# SCH_esp32car_2026-05-05.net
KiCad netlist of a schematic drawn in EasyEDA
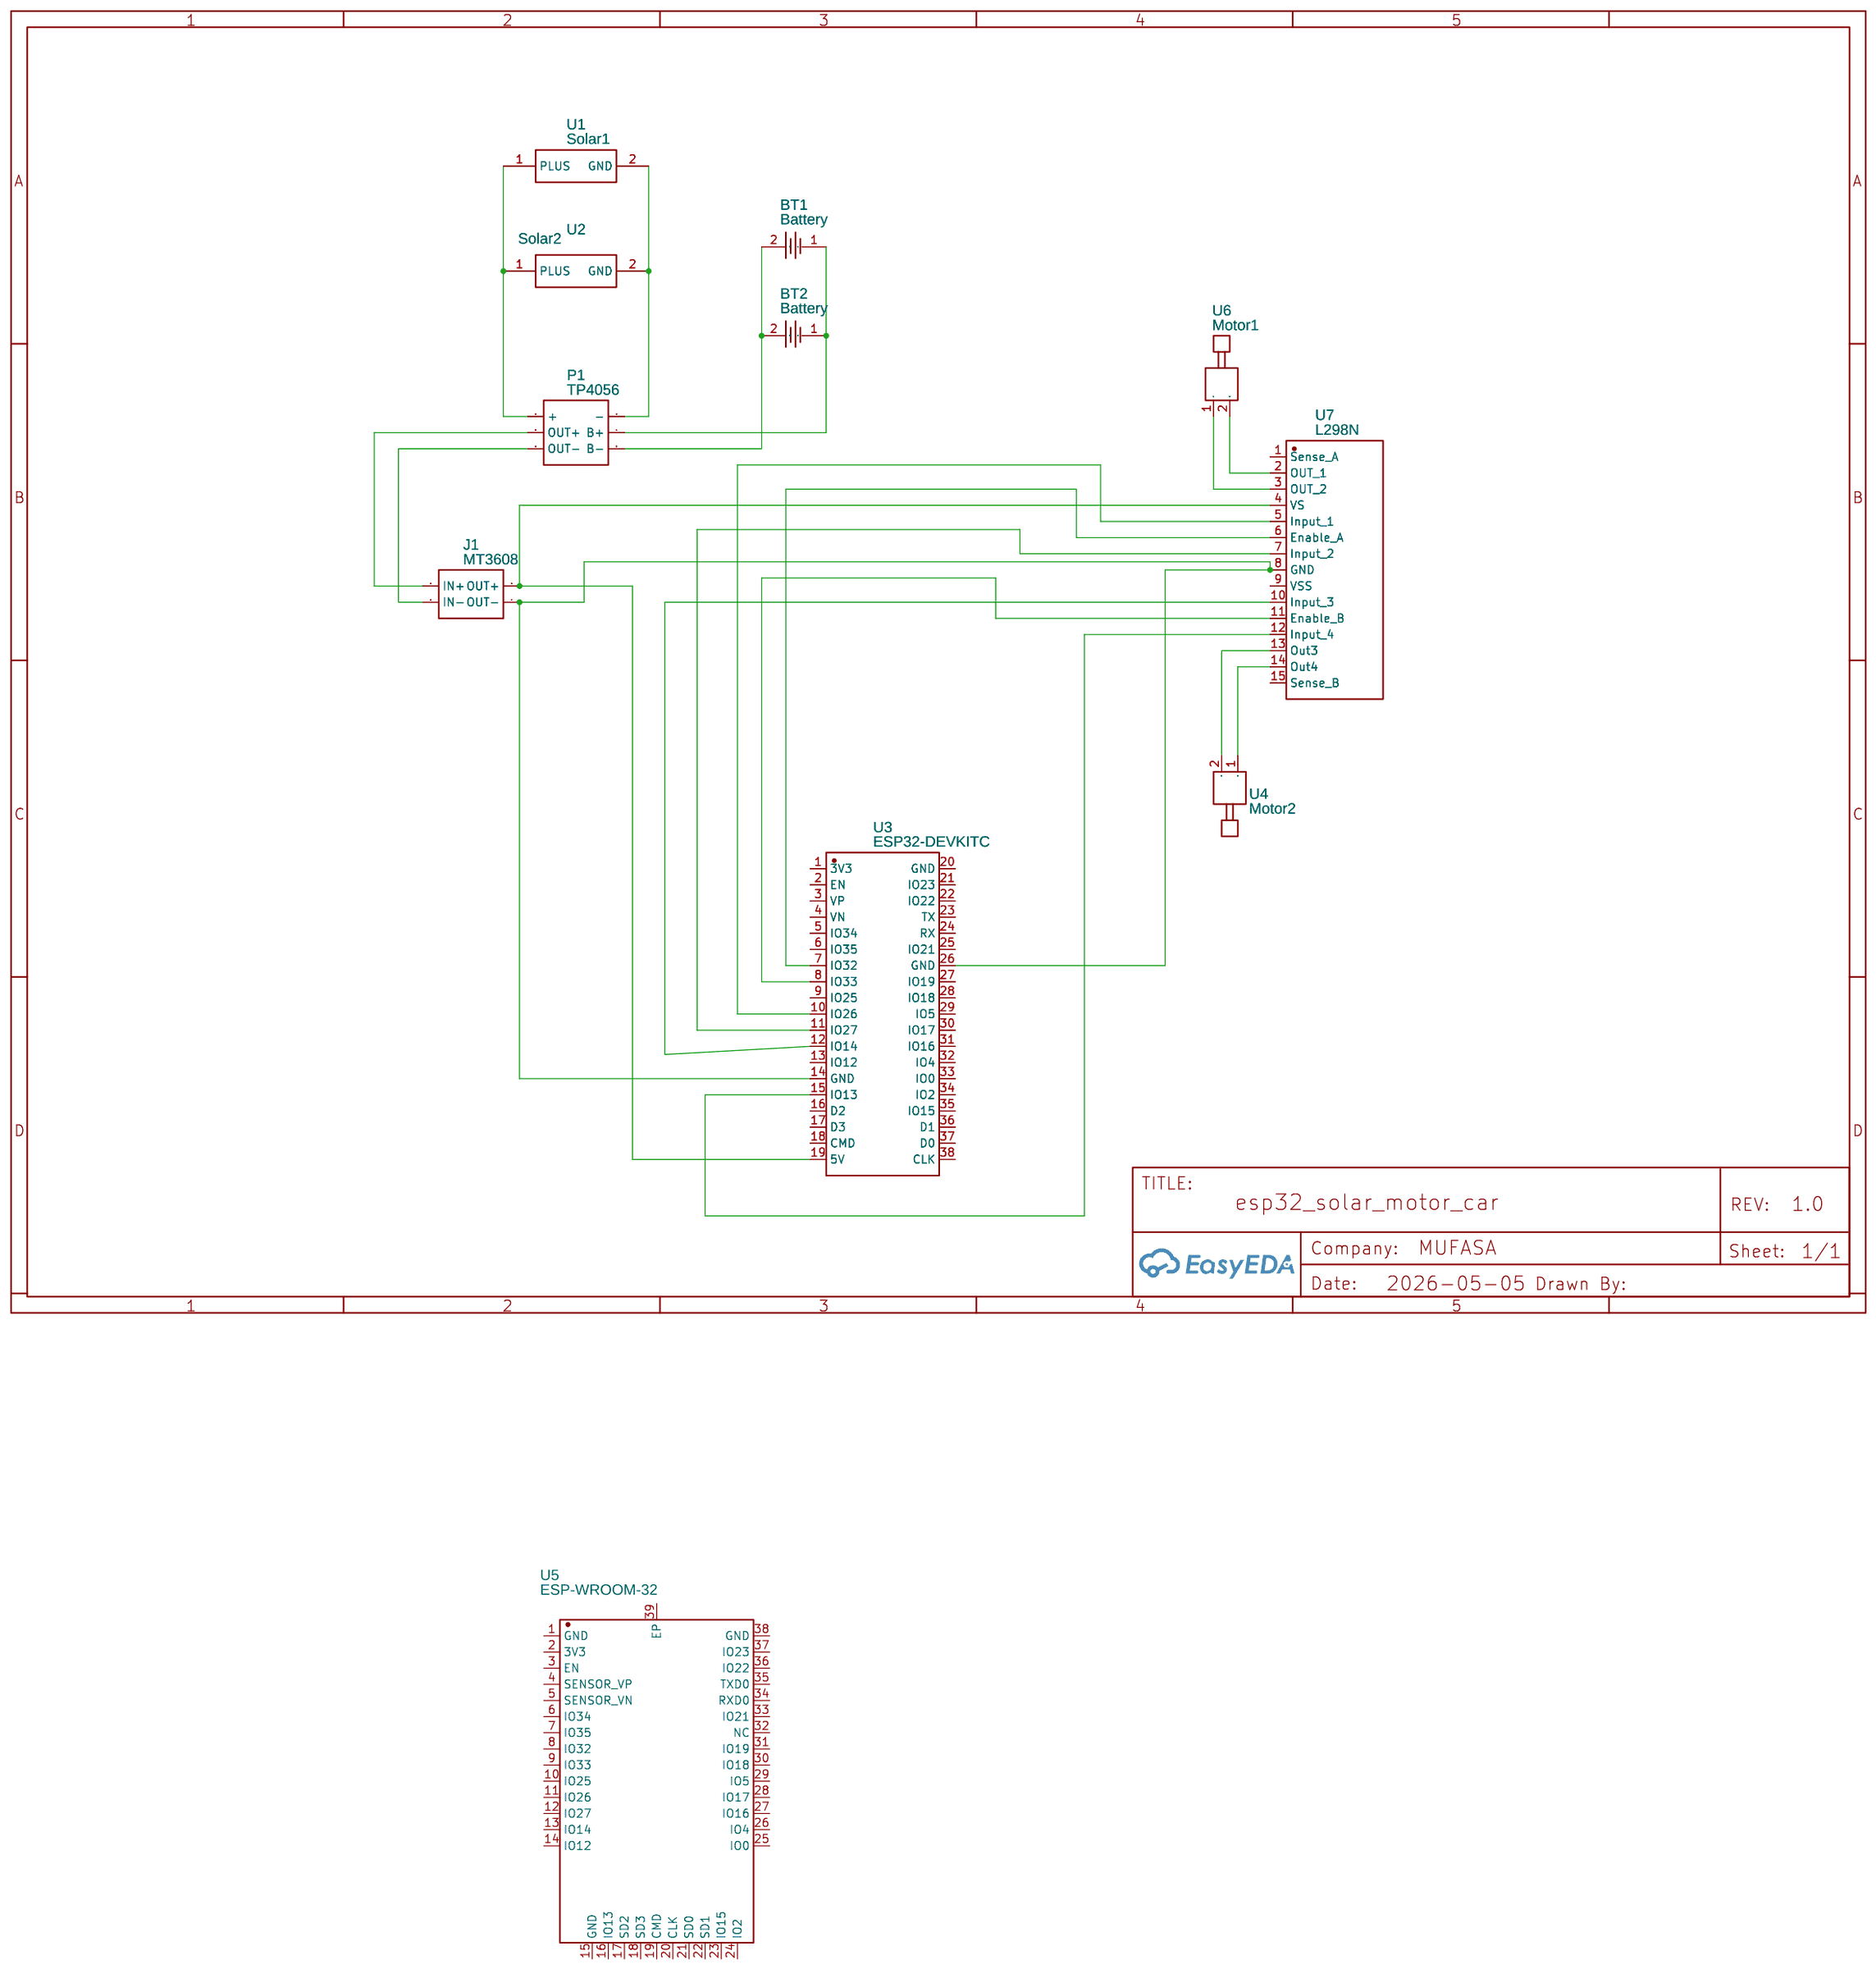
[diagram p0: schematic sheet]

(export (version "E")
  (design (tool "Eeschema 10.0.6"))
  (components
    (comp (ref "BT1")
      (value "Battery")
      (fields
        (field (name "Manufacturer Part") "BH-18650-B1BA002")
        (field (name "Manufacturer") "MYOUNG(美阳)")
      )
      (libsource (lib "") (part "BH-18650-B1BA002"))
    )
    (comp (ref "BT2")
      (value "Battery")
      (fields
        (field (name "Manufacturer Part") "BH-18650-B1BA002")
        (field (name "Manufacturer") "MYOUNG(美阳)")
      )
      (libsource (lib "") (part "BH-18650-B1BA002"))
    )
    (comp (ref "J1") (value "MT3608") (libsource (lib "") (part "HDR-M-2.54_2x2")))
    (comp (ref "P1")
      (value "TP4056")
      (fields (field (name "Manufacturer Part") "2X3 2.54mm IDC Box") (field (name "Manufacturer") "BOOMELE"))
      (libsource (lib "") (part "HDR-IDC-2.54-2X3P"))
    )
    (comp (ref "U1") (value "Solar1") (libsource (lib "") (part "KXOB25-01X8F-TB")))
    (comp (ref "U2") (value "Solar2") (libsource (lib "") (part "KXOB25-01X8F-TB")))
    (comp (ref "U3")
      (value "ESP32-DEVKITC")
      (fields
        (field (name "Manufacturer Part") "ESP32-DevKitC")
        (field (name "Manufacturer") "ESPRESSIF(乐鑫)")
      )
      (libsource (lib "") (part "ESP32-DEVKITC"))
    )
    (comp (ref "U4")
      (value "Motor2")
      (fields (field (name "Manufacturer Part") "LCM04084521-B1") (field (name "Manufacturer") "LEADER(立得)"))
      (libsource (lib "") (part "LCM04084521-B1_1"))
    )
    (comp (ref "U5")
      (value "ESP-WROOM-32")
      (fields
        (field (name "Manufacturer Part") "ESP32-WROOM-32")
        (field (name "Manufacturer") "ESPRESSIF(乐鑫)")
      )
      (libsource (lib "") (part "ESP-WROOM-32"))
    )
    (comp (ref "U6")
      (value "Motor1")
      (fields (field (name "Manufacturer Part") "LCM04084521-B1") (field (name "Manufacturer") "LEADER(立得)"))
      (libsource (lib "") (part "LCM04084521-B1"))
    )
    (comp (ref "U7")
      (value "L298N")
      (fields (field (name "Manufacturer") "HGSEMI(华冠)"))
      (libsource (lib "") (part "L298N"))
    )
  )
  (nets
    (net (code "1") (name "Net-(J1-IN+)") (class "Default")
      (node (ref "J1") (pin "1") (pinfunction "IN+_1") (pintype "input"))
      (node (ref "P1") (pin "3") (pinfunction "OUT+_3") (pintype "output"))
    )
    (net (code "2") (name "Net-(J1-IN-)") (class "Default")
      (node (ref "J1") (pin "3") (pinfunction "IN-_3") (pintype "input"))
      (node (ref "P1") (pin "5") (pinfunction "OUT-_5") (pintype "output"))
    )
    (net (code "3") (name "Net-(J1-OUT+)") (class "Default")
      (node (ref "J1") (pin "2") (pinfunction "OUT+_2") (pintype "output"))
      (node (ref "U3") (pin "19") (pinfunction "5V_19") (pintype "unspecified"))
      (node (ref "U7") (pin "4") (pinfunction "VS_4") (pintype "unspecified"))
    )
    (net (code "4") (name "Net-(J1-OUT-)") (class "Default")
      (node (ref "J1") (pin "4") (pinfunction "OUT-_4") (pintype "output"))
      (node (ref "U3") (pin "14") (pinfunction "GND_14") (pintype "unspecified"))
      (node (ref "U3") (pin "26") (pinfunction "GND_26") (pintype "unspecified"))
      (node (ref "U7") (pin "8") (pinfunction "GND_8") (pintype "unspecified"))
    )
    (net (code "5") (name "Net-(P1-+)") (class "Default")
      (node (ref "P1") (pin "1") (pinfunction "+_1") (pintype "unspecified"))
      (node (ref "U1") (pin "1") (pinfunction "PLUS_1") (pintype "unspecified"))
      (node (ref "U2") (pin "1") (pinfunction "PLUS_1") (pintype "unspecified"))
    )
    (net (code "6") (name "Net-(P1--)") (class "Default")
      (node (ref "P1") (pin "2") (pinfunction "-_2") (pintype "unspecified"))
      (node (ref "U1") (pin "2") (pinfunction "GND_2") (pintype "unspecified"))
      (node (ref "U2") (pin "2") (pinfunction "GND_2") (pintype "unspecified"))
    )
    (net (code "7") (name "Net-(P1-B+)") (class "Default")
      (node (ref "BT1") (pin "1") (pinfunction "1_1") (pintype "input"))
      (node (ref "BT2") (pin "1") (pinfunction "1_1") (pintype "input"))
      (node (ref "P1") (pin "4") (pinfunction "B+_4") (pintype "unspecified"))
    )
    (net (code "8") (name "Net-(P1-B-)") (class "Default")
      (node (ref "BT1") (pin "2") (pinfunction "2_2") (pintype "input"))
      (node (ref "BT2") (pin "2") (pinfunction "2_2") (pintype "input"))
      (node (ref "P1") (pin "6") (pinfunction "B-_6") (pintype "unspecified"))
    )
    (net (code "9") (name "Net-(U3-IO13)") (class "Default")
      (node (ref "U3") (pin "15") (pinfunction "IO13_15") (pintype "unspecified"))
      (node (ref "U7") (pin "12") (pinfunction "Input_4_12") (pintype "unspecified"))
    )
    (net (code "10") (name "Net-(U3-IO14)") (class "Default")
      (node (ref "U3") (pin "12") (pinfunction "IO14_12") (pintype "unspecified"))
      (node (ref "U7") (pin "10") (pinfunction "Input_3_10") (pintype "unspecified"))
    )
    (net (code "11") (name "Net-(U3-IO26)") (class "Default")
      (node (ref "U3") (pin "10") (pinfunction "IO26_10") (pintype "unspecified"))
      (node (ref "U7") (pin "5") (pinfunction "Input_1_5") (pintype "unspecified"))
    )
    (net (code "12") (name "Net-(U3-IO27)") (class "Default")
      (node (ref "U3") (pin "11") (pinfunction "IO27_11") (pintype "unspecified"))
      (node (ref "U7") (pin "7") (pinfunction "Input_2_7") (pintype "unspecified"))
    )
    (net (code "13") (name "Net-(U3-IO32)") (class "Default")
      (node (ref "U3") (pin "7") (pinfunction "IO32_7") (pintype "unspecified"))
      (node (ref "U7") (pin "6") (pinfunction "Enable_A_6") (pintype "unspecified"))
    )
    (net (code "14") (name "Net-(U3-IO33)") (class "Default")
      (node (ref "U3") (pin "8") (pinfunction "IO33_8") (pintype "unspecified"))
      (node (ref "U7") (pin "11") (pinfunction "Enable_B_11") (pintype "unspecified"))
    )
    (net (code "15") (name "Net-(U7-OUT_1)") (class "Default")
      (node (ref "U6") (pin "2") (pinfunction "2_2") (pintype "unspecified"))
      (node (ref "U7") (pin "2") (pinfunction "OUT_1_2") (pintype "unspecified"))
    )
    (net (code "16") (name "Net-(U7-OUT_2)") (class "Default")
      (node (ref "U6") (pin "1") (pinfunction "1_1") (pintype "unspecified"))
      (node (ref "U7") (pin "3") (pinfunction "OUT_2_3") (pintype "unspecified"))
    )
    (net (code "17") (name "Net-(U7-Out3)") (class "Default")
      (node (ref "U4") (pin "2") (pinfunction "2_2") (pintype "unspecified"))
      (node (ref "U7") (pin "13") (pinfunction "Out3_13") (pintype "unspecified"))
    )
    (net (code "18") (name "Net-(U7-Out4)") (class "Default")
      (node (ref "U4") (pin "1") (pinfunction "1_1") (pintype "unspecified"))
      (node (ref "U7") (pin "14") (pinfunction "Out4_14") (pintype "unspecified"))
    )
    (net (code "19") (name "unconnected-(U3-3V3-Pad1)") (class "Default")
      (node (ref "U3") (pin "1") (pinfunction "3V3_1") (pintype "unspecified"))
    )
    (net (code "20") (name "unconnected-(U3-CLK-Pad38)") (class "Default")
      (node (ref "U3") (pin "38") (pinfunction "CLK_38") (pintype "unspecified"))
    )
    (net (code "21") (name "unconnected-(U3-CMD-Pad18)") (class "Default")
      (node (ref "U3") (pin "18") (pinfunction "CMD_18") (pintype "unspecified"))
    )
    (net (code "22") (name "unconnected-(U3-D0-Pad37)") (class "Default")
      (node (ref "U3") (pin "37") (pinfunction "D0_37") (pintype "unspecified"))
    )
    (net (code "23") (name "unconnected-(U3-D1-Pad36)") (class "Default")
      (node (ref "U3") (pin "36") (pinfunction "D1_36") (pintype "unspecified"))
    )
    (net (code "24") (name "unconnected-(U3-D2-Pad16)") (class "Default")
      (node (ref "U3") (pin "16") (pinfunction "D2_16") (pintype "unspecified"))
    )
    (net (code "25") (name "unconnected-(U3-D3-Pad17)") (class "Default")
      (node (ref "U3") (pin "17") (pinfunction "D3_17") (pintype "unspecified"))
    )
    (net (code "26") (name "unconnected-(U3-EN-Pad2)") (class "Default")
      (node (ref "U3") (pin "2") (pinfunction "EN_2") (pintype "unspecified"))
    )
    (net (code "27") (name "unconnected-(U3-GND-Pad20)") (class "Default")
      (node (ref "U3") (pin "20") (pinfunction "GND_20") (pintype "unspecified"))
    )
    (net (code "28") (name "unconnected-(U3-IO0-Pad33)") (class "Default")
      (node (ref "U3") (pin "33") (pinfunction "IO0_33") (pintype "unspecified"))
    )
    (net (code "29") (name "unconnected-(U3-IO2-Pad34)") (class "Default")
      (node (ref "U3") (pin "34") (pinfunction "IO2_34") (pintype "unspecified"))
    )
    (net (code "30") (name "unconnected-(U3-IO4-Pad32)") (class "Default")
      (node (ref "U3") (pin "32") (pinfunction "IO4_32") (pintype "unspecified"))
    )
    (net (code "31") (name "unconnected-(U3-IO5-Pad29)") (class "Default")
      (node (ref "U3") (pin "29") (pinfunction "IO5_29") (pintype "unspecified"))
    )
    (net (code "32") (name "unconnected-(U3-IO12-Pad13)") (class "Default")
      (node (ref "U3") (pin "13") (pinfunction "IO12_13") (pintype "unspecified"))
    )
    (net (code "33") (name "unconnected-(U3-IO15-Pad35)") (class "Default")
      (node (ref "U3") (pin "35") (pinfunction "IO15_35") (pintype "unspecified"))
    )
    (net (code "34") (name "unconnected-(U3-IO16-Pad31)") (class "Default")
      (node (ref "U3") (pin "31") (pinfunction "IO16_31") (pintype "unspecified"))
    )
    (net (code "35") (name "unconnected-(U3-IO17-Pad30)") (class "Default")
      (node (ref "U3") (pin "30") (pinfunction "IO17_30") (pintype "unspecified"))
    )
    (net (code "36") (name "unconnected-(U3-IO18-Pad28)") (class "Default")
      (node (ref "U3") (pin "28") (pinfunction "IO18_28") (pintype "unspecified"))
    )
    (net (code "37") (name "unconnected-(U3-IO19-Pad27)") (class "Default")
      (node (ref "U3") (pin "27") (pinfunction "IO19_27") (pintype "unspecified"))
    )
    (net (code "38") (name "unconnected-(U3-IO21-Pad25)") (class "Default")
      (node (ref "U3") (pin "25") (pinfunction "IO21_25") (pintype "unspecified"))
    )
    (net (code "39") (name "unconnected-(U3-IO22-Pad22)") (class "Default")
      (node (ref "U3") (pin "22") (pinfunction "IO22_22") (pintype "unspecified"))
    )
    (net (code "40") (name "unconnected-(U3-IO23-Pad21)") (class "Default")
      (node (ref "U3") (pin "21") (pinfunction "IO23_21") (pintype "unspecified"))
    )
    (net (code "41") (name "unconnected-(U3-IO25-Pad9)") (class "Default")
      (node (ref "U3") (pin "9") (pinfunction "IO25_9") (pintype "unspecified"))
    )
    (net (code "42") (name "unconnected-(U3-IO34-Pad5)") (class "Default")
      (node (ref "U3") (pin "5") (pinfunction "IO34_5") (pintype "unspecified"))
    )
    (net (code "43") (name "unconnected-(U3-IO35-Pad6)") (class "Default")
      (node (ref "U3") (pin "6") (pinfunction "IO35_6") (pintype "unspecified"))
    )
    (net (code "44") (name "unconnected-(U3-RX-Pad24)") (class "Default")
      (node (ref "U3") (pin "24") (pinfunction "RX_24") (pintype "unspecified"))
    )
    (net (code "45") (name "unconnected-(U3-TX-Pad23)") (class "Default")
      (node (ref "U3") (pin "23") (pinfunction "TX_23") (pintype "unspecified"))
    )
    (net (code "46") (name "unconnected-(U3-VN-Pad4)") (class "Default")
      (node (ref "U3") (pin "4") (pinfunction "VN_4") (pintype "unspecified"))
    )
    (net (code "47") (name "unconnected-(U3-VP-Pad3)") (class "Default")
      (node (ref "U3") (pin "3") (pinfunction "VP_3") (pintype "unspecified"))
    )
    (net (code "48") (name "unconnected-(U5-3V3-Pad2)") (class "Default")
      (node (ref "U5") (pin "2") (pinfunction "3V3_2") (pintype "unspecified"))
    )
    (net (code "49") (name "unconnected-(U5-CLK-Pad20)") (class "Default")
      (node (ref "U5") (pin "20") (pinfunction "CLK_20") (pintype "unspecified"))
    )
    (net (code "50") (name "unconnected-(U5-CMD-Pad19)") (class "Default")
      (node (ref "U5") (pin "19") (pinfunction "CMD_19") (pintype "unspecified"))
    )
    (net (code "51") (name "unconnected-(U5-EN-Pad3)") (class "Default")
      (node (ref "U5") (pin "3") (pinfunction "EN_3") (pintype "unspecified"))
    )
    (net (code "52") (name "unconnected-(U5-EP-Pad39)") (class "Default")
      (node (ref "U5") (pin "39") (pinfunction "EP_39") (pintype "unspecified"))
    )
    (net (code "53") (name "unconnected-(U5-GND-Pad1)") (class "Default")
      (node (ref "U5") (pin "1") (pinfunction "GND_1") (pintype "unspecified"))
    )
    (net (code "54") (name "unconnected-(U5-GND-Pad15)") (class "Default")
      (node (ref "U5") (pin "15") (pinfunction "GND_15") (pintype "unspecified"))
    )
    (net (code "55") (name "unconnected-(U5-GND-Pad38)") (class "Default")
      (node (ref "U5") (pin "38") (pinfunction "GND_38") (pintype "unspecified"))
    )
    (net (code "56") (name "unconnected-(U5-IO0-Pad25)") (class "Default")
      (node (ref "U5") (pin "25") (pinfunction "IO0_25") (pintype "unspecified"))
    )
    (net (code "57") (name "unconnected-(U5-IO2-Pad24)") (class "Default")
      (node (ref "U5") (pin "24") (pinfunction "IO2_24") (pintype "unspecified"))
    )
    (net (code "58") (name "unconnected-(U5-IO4-Pad26)") (class "Default")
      (node (ref "U5") (pin "26") (pinfunction "IO4_26") (pintype "unspecified"))
    )
    (net (code "59") (name "unconnected-(U5-IO5-Pad29)") (class "Default")
      (node (ref "U5") (pin "29") (pinfunction "IO5_29") (pintype "unspecified"))
    )
    (net (code "60") (name "unconnected-(U5-IO12-Pad14)") (class "Default")
      (node (ref "U5") (pin "14") (pinfunction "IO12_14") (pintype "unspecified"))
    )
    (net (code "61") (name "unconnected-(U5-IO13-Pad16)") (class "Default")
      (node (ref "U5") (pin "16") (pinfunction "IO13_16") (pintype "unspecified"))
    )
    (net (code "62") (name "unconnected-(U5-IO14-Pad13)") (class "Default")
      (node (ref "U5") (pin "13") (pinfunction "IO14_13") (pintype "unspecified"))
    )
    (net (code "63") (name "unconnected-(U5-IO15-Pad23)") (class "Default")
      (node (ref "U5") (pin "23") (pinfunction "IO15_23") (pintype "unspecified"))
    )
    (net (code "64") (name "unconnected-(U5-IO16-Pad27)") (class "Default")
      (node (ref "U5") (pin "27") (pinfunction "IO16_27") (pintype "unspecified"))
    )
    (net (code "65") (name "unconnected-(U5-IO17-Pad28)") (class "Default")
      (node (ref "U5") (pin "28") (pinfunction "IO17_28") (pintype "unspecified"))
    )
    (net (code "66") (name "unconnected-(U5-IO18-Pad30)") (class "Default")
      (node (ref "U5") (pin "30") (pinfunction "IO18_30") (pintype "unspecified"))
    )
    (net (code "67") (name "unconnected-(U5-IO19-Pad31)") (class "Default")
      (node (ref "U5") (pin "31") (pinfunction "IO19_31") (pintype "unspecified"))
    )
    (net (code "68") (name "unconnected-(U5-IO21-Pad33)") (class "Default")
      (node (ref "U5") (pin "33") (pinfunction "IO21_33") (pintype "unspecified"))
    )
    (net (code "69") (name "unconnected-(U5-IO22-Pad36)") (class "Default")
      (node (ref "U5") (pin "36") (pinfunction "IO22_36") (pintype "unspecified"))
    )
    (net (code "70") (name "unconnected-(U5-IO23-Pad37)") (class "Default")
      (node (ref "U5") (pin "37") (pinfunction "IO23_37") (pintype "unspecified"))
    )
    (net (code "71") (name "unconnected-(U5-IO25-Pad10)") (class "Default")
      (node (ref "U5") (pin "10") (pinfunction "IO25_10") (pintype "unspecified"))
    )
    (net (code "72") (name "unconnected-(U5-IO26-Pad11)") (class "Default")
      (node (ref "U5") (pin "11") (pinfunction "IO26_11") (pintype "unspecified"))
    )
    (net (code "73") (name "unconnected-(U5-IO27-Pad12)") (class "Default")
      (node (ref "U5") (pin "12") (pinfunction "IO27_12") (pintype "unspecified"))
    )
    (net (code "74") (name "unconnected-(U5-IO32-Pad8)") (class "Default")
      (node (ref "U5") (pin "8") (pinfunction "IO32_8") (pintype "unspecified"))
    )
    (net (code "75") (name "unconnected-(U5-IO33-Pad9)") (class "Default")
      (node (ref "U5") (pin "9") (pinfunction "IO33_9") (pintype "unspecified"))
    )
    (net (code "76") (name "unconnected-(U5-IO34-Pad6)") (class "Default")
      (node (ref "U5") (pin "6") (pinfunction "IO34_6") (pintype "unspecified"))
    )
    (net (code "77") (name "unconnected-(U5-IO35-Pad7)") (class "Default")
      (node (ref "U5") (pin "7") (pinfunction "IO35_7") (pintype "unspecified"))
    )
    (net (code "78") (name "unconnected-(U5-NC-Pad32)") (class "Default")
      (node (ref "U5") (pin "32") (pinfunction "NC_32") (pintype "unspecified"))
    )
    (net (code "79") (name "unconnected-(U5-RXD0-Pad34)") (class "Default")
      (node (ref "U5") (pin "34") (pinfunction "RXD0_34") (pintype "unspecified"))
    )
    (net (code "80") (name "unconnected-(U5-SD0-Pad21)") (class "Default")
      (node (ref "U5") (pin "21") (pinfunction "SD0_21") (pintype "unspecified"))
    )
    (net (code "81") (name "unconnected-(U5-SD1-Pad22)") (class "Default")
      (node (ref "U5") (pin "22") (pinfunction "SD1_22") (pintype "unspecified"))
    )
    (net (code "82") (name "unconnected-(U5-SD2-Pad17)") (class "Default")
      (node (ref "U5") (pin "17") (pinfunction "SD2_17") (pintype "unspecified"))
    )
    (net (code "83") (name "unconnected-(U5-SD3-Pad18)") (class "Default")
      (node (ref "U5") (pin "18") (pinfunction "SD3_18") (pintype "unspecified"))
    )
    (net (code "84") (name "unconnected-(U5-SENSOR_VN-Pad5)") (class "Default")
      (node (ref "U5") (pin "5") (pinfunction "SENSOR_VN_5") (pintype "unspecified"))
    )
    (net (code "85") (name "unconnected-(U5-SENSOR_VP-Pad4)") (class "Default")
      (node (ref "U5") (pin "4") (pinfunction "SENSOR_VP_4") (pintype "unspecified"))
    )
    (net (code "86") (name "unconnected-(U5-TXD0-Pad35)") (class "Default")
      (node (ref "U5") (pin "35") (pinfunction "TXD0_35") (pintype "unspecified"))
    )
    (net (code "87") (name "unconnected-(U7-Sense_A-Pad1)") (class "Default")
      (node (ref "U7") (pin "1") (pinfunction "Sense_A_1") (pintype "unspecified"))
    )
    (net (code "88") (name "unconnected-(U7-Sense_B-Pad15)") (class "Default")
      (node (ref "U7") (pin "15") (pinfunction "Sense_B_15") (pintype "unspecified"))
    )
    (net (code "89") (name "unconnected-(U7-VSS-Pad9)") (class "Default")
      (node (ref "U7") (pin "9") (pinfunction "VSS_9") (pintype "unspecified"))
    )
  )
)
